# SCH_smart_golf_ball_v2_2024-06-10.net
KiCad netlist of a schematic drawn in EasyEDA
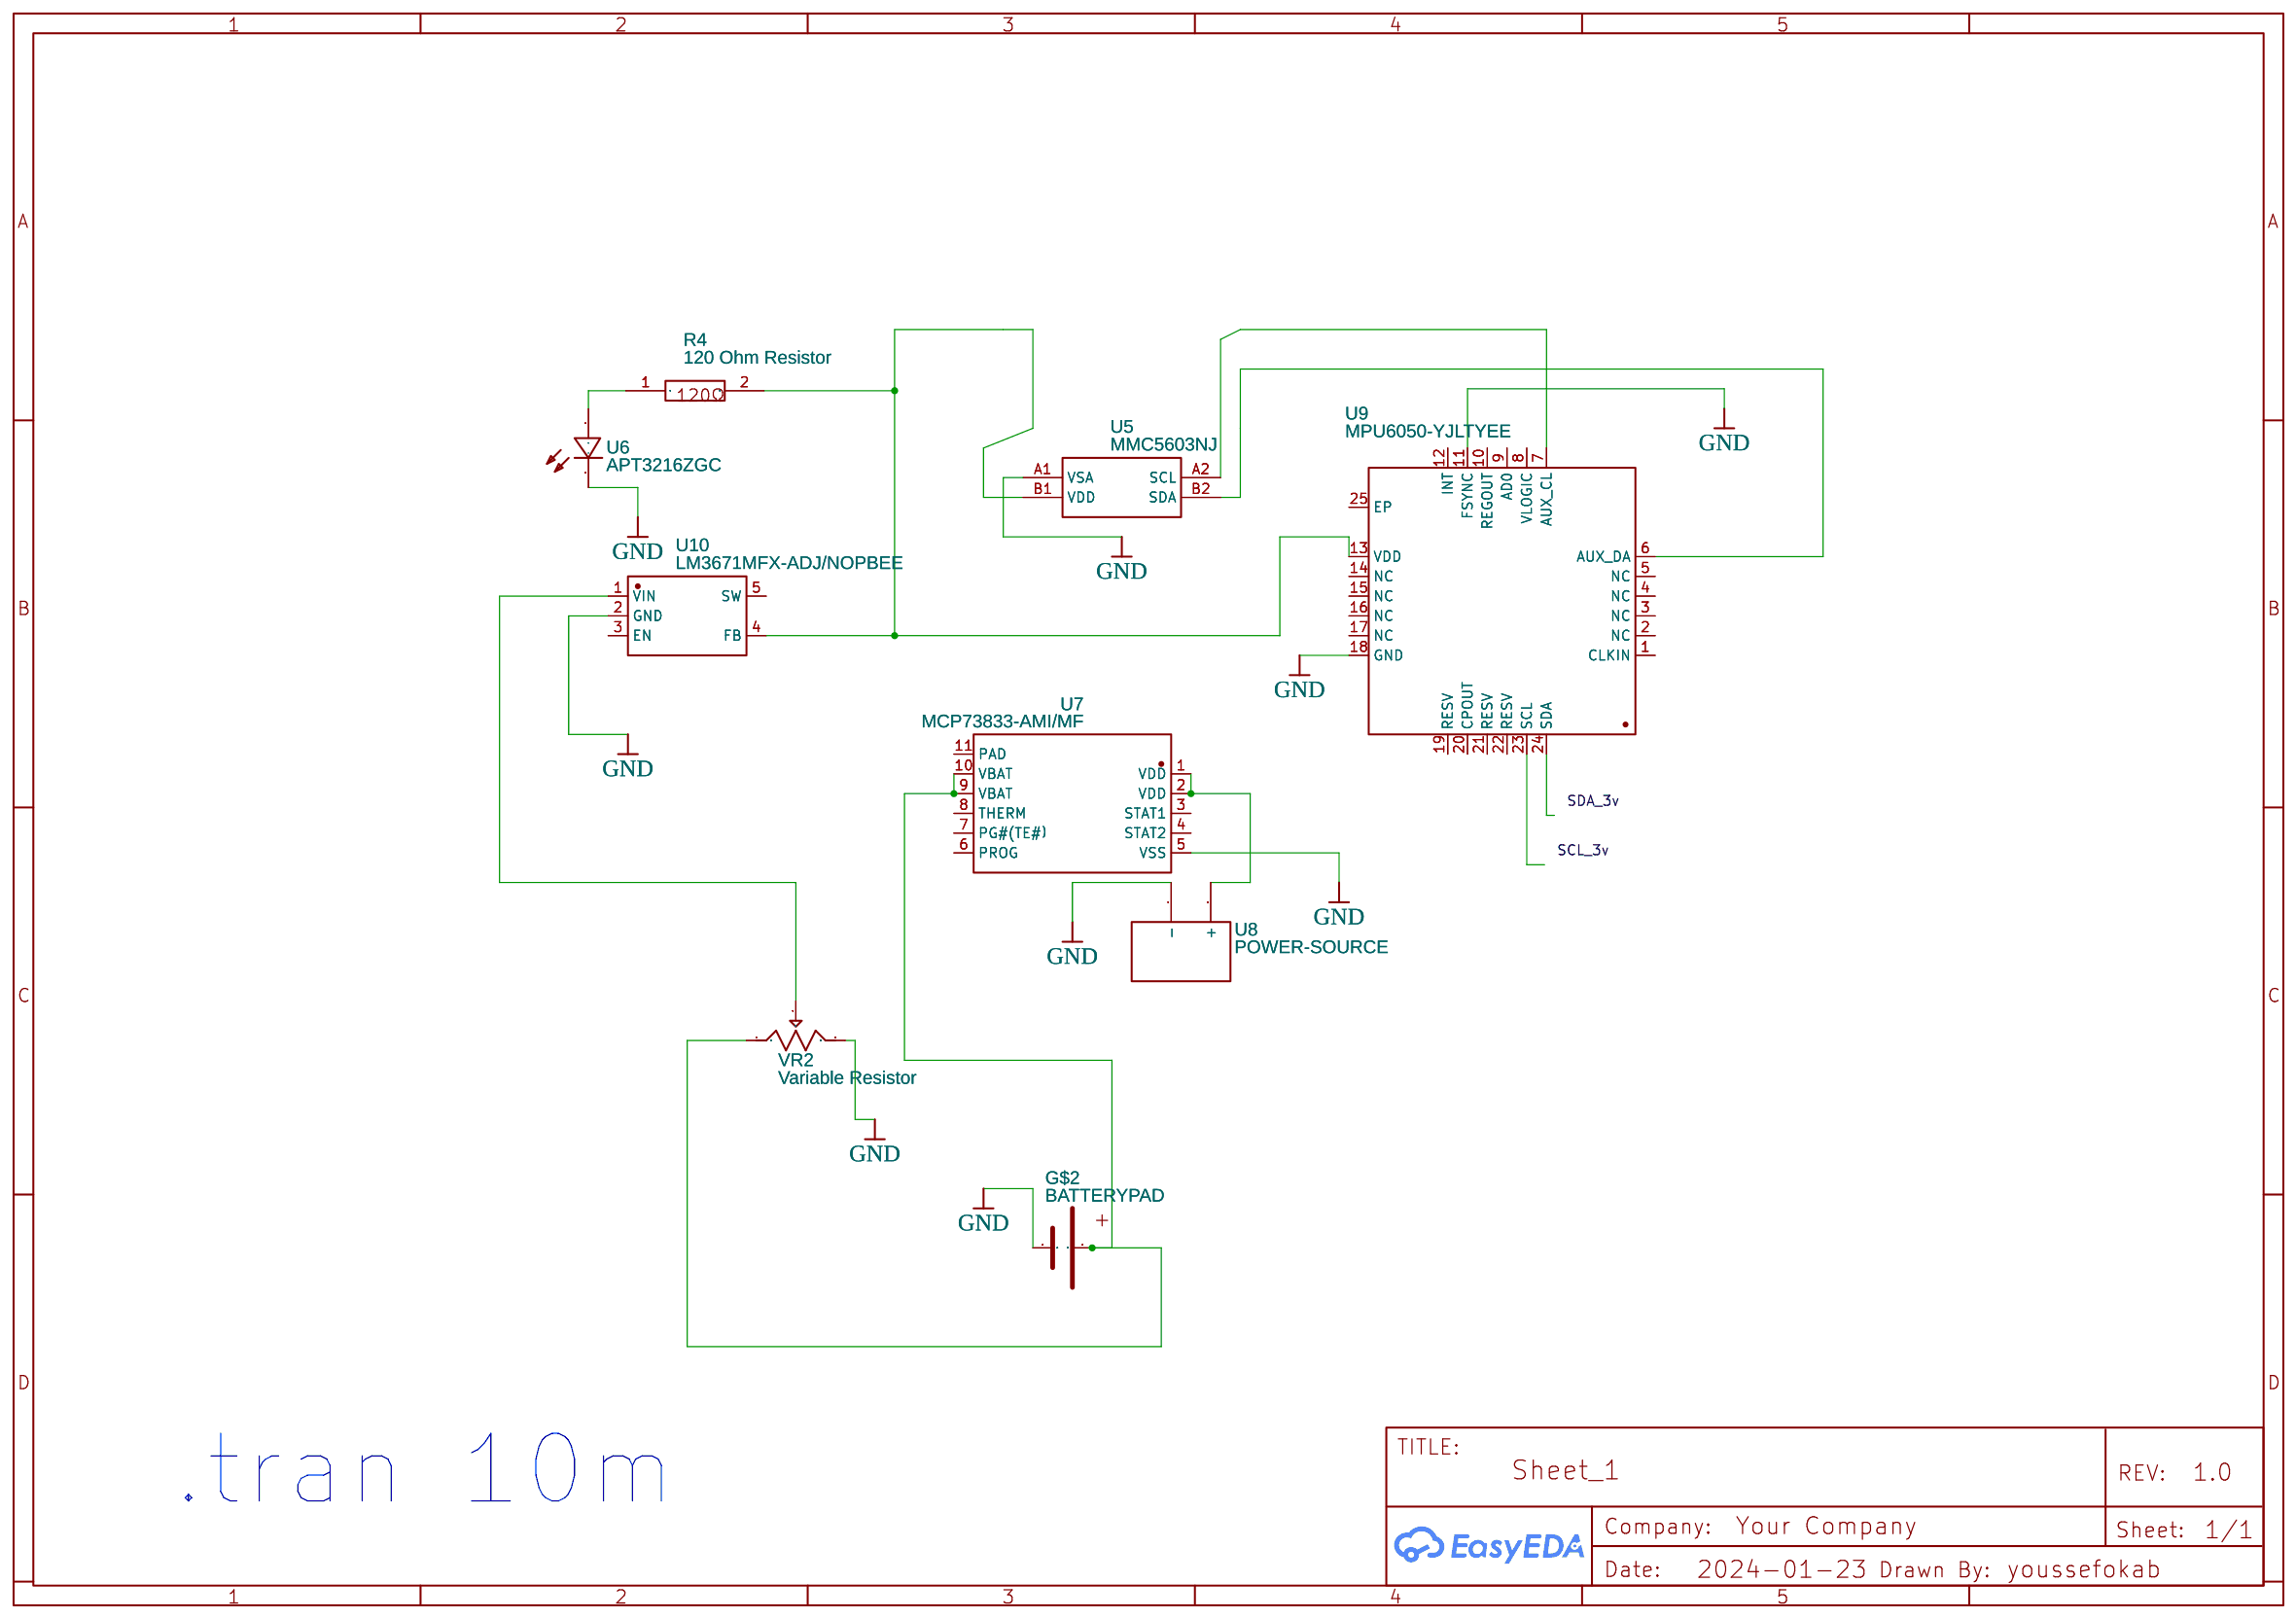
[diagram p0: schematic sheet]

(export (version "E")
  (design (tool "Eeschema 10.0.6"))
  (components
    (comp (ref "G$2") (value "BATTERYPAD") (libsource (lib "") (part "BATTERYPAD")))
    (comp (ref "R4") (value "120 Ohm Resistor") (libsource (lib "") (part "120 Ohm Resistor")))
    (comp (ref "U5")
      (value "MMC5603NJ")
      (fields (field (name "Manufacturer") "MEMSIC(美新)"))
      (libsource (lib "") (part "MMC5603NJ"))
    )
    (comp (ref "U6")
      (value "APT3216ZGC")
      (fields (field (name "Manufacturer") "Kingbright"))
      (libsource (lib "") (part "APT3216ZGC"))
    )
    (comp (ref "U7")
      (value "MCP73833-AMI/MF")
      (fields (field (name "Manufacturer") "MICROCHIP(美国微芯)"))
      (libsource (lib "") (part "MCP73833-AMI/MF"))
    )
    (comp (ref "U8") (value "POWER-SOURCE") (libsource (lib "") (part "POWER-SOURCE")))
    (comp (ref "U9")
      (value "MPU6050-YJLTYEE")
      (fields (field (name "Manufacturer Part") "MPU6050-YJLTY"))
      (libsource (lib "") (part "MPU6050-YJLTY"))
    )
    (comp (ref "U10")
      (value "LM3671MFX-ADJ/NOPBEE")
      (fields
        (field (name "Manufacturer Part") "LM3671MFX-ADJ/NOPB")
        (field (name "Manufacturer") "TI(德州仪器)")
      )
      (libsource (lib "") (part "LM3671MFX-ADJ/NOPB"))
    )
    (comp (ref "VR2")
      (value "Variable Resistor")
      (fields (field (name "Manufacturer Part") "x1"))
      (libsource (lib "") (part "Variable Resistor"))
    )
  )
  (nets
    (net (code "3") (name "GND") (class "Default")
      (node (ref "G$2") (pin "-VE") (pinfunction "-VE_-VE") (pintype "bidirectional"))
      (node (ref "U10") (pin "2") (pinfunction "GND_2") (pintype "unspecified"))
      (node (ref "U5") (pin "A1") (pinfunction "VSA_A1") (pintype "unspecified"))
      (node (ref "U6") (pin "1") (pinfunction "-_1") (pintype "unspecified"))
      (node (ref "U7") (pin "5") (pinfunction "VSS_5") (pintype "unspecified"))
      (node (ref "U8") (pin "1") (pinfunction "-_1") (pintype "unspecified"))
      (node (ref "U9") (pin "11") (pinfunction "FSYNC_11") (pintype "unspecified"))
      (node (ref "U9") (pin "18") (pinfunction "GND_18") (pintype "unspecified"))
      (node (ref "VR2") (pin "3") (pinfunction "3_3") (pintype "unspecified"))
    )
    (net (code "4") (name "Net-(G$2-Pad+VE)") (class "Default")
      (node (ref "G$2") (pin "+VE") (pinfunction "+VE_+VE") (pintype "bidirectional"))
      (node (ref "U7") (pin "10") (pinfunction "VBAT_10") (pintype "unspecified"))
      (node (ref "U7") (pin "9") (pinfunction "VBAT_9") (pintype "unspecified"))
      (node (ref "VR2") (pin "1") (pinfunction "1_1") (pintype "unspecified"))
    )
    (net (code "5") (name "Net-(U5-SCL)") (class "Default")
      (node (ref "U5") (pin "A2") (pinfunction "SCL_A2") (pintype "unspecified"))
      (node (ref "U9") (pin "7") (pinfunction "AUX_CL_7") (pintype "unspecified"))
    )
    (net (code "6") (name "Net-(U5-SDA)") (class "Default")
      (node (ref "U5") (pin "B2") (pinfunction "SDA_B2") (pintype "unspecified"))
      (node (ref "U9") (pin "6") (pinfunction "AUX_DA_6") (pintype "unspecified"))
    )
    (net (code "7") (name "Net-(U6-+)") (class "Default")
      (node (ref "R4") (pin "1") (pinfunction "1_1") (pintype "unspecified"))
      (node (ref "U6") (pin "2") (pinfunction "+_2") (pintype "unspecified"))
    )
    (net (code "8") (name "Net-(U8-+)") (class "Default")
      (node (ref "U7") (pin "1") (pinfunction "VDD_1") (pintype "unspecified"))
      (node (ref "U7") (pin "2") (pinfunction "VDD_2") (pintype "unspecified"))
      (node (ref "U8") (pin "2") (pinfunction "+_2") (pintype "unspecified"))
    )
    (net (code "9") (name "Net-(U10-FB)") (class "Default")
      (node (ref "R4") (pin "2") (pinfunction "2_2") (pintype "unspecified"))
      (node (ref "U10") (pin "4") (pinfunction "FB_4") (pintype "unspecified"))
      (node (ref "U5") (pin "B1") (pinfunction "VDD_B1") (pintype "unspecified"))
      (node (ref "U9") (pin "13") (pinfunction "VDD_13") (pintype "unspecified"))
    )
    (net (code "10") (name "Net-(U10-VIN)") (class "Default")
      (node (ref "U10") (pin "1") (pinfunction "VIN_1") (pintype "unspecified"))
      (node (ref "VR2") (pin "2") (pinfunction "2_2") (pintype "unspecified"))
    )
    (net (code "11") (name "unconnected-(U7-PAD-Pad11)") (class "Default")
      (node (ref "U7") (pin "11") (pinfunction "PAD_11") (pintype "unspecified"))
    )
    (net (code "12") (name "unconnected-(U7-PG#(TE#）-Pad7)") (class "Default")
      (node (ref "U7") (pin "7") (pinfunction "PG#(TE#）_7") (pintype "unspecified"))
    )
    (net (code "13") (name "unconnected-(U7-PROG-Pad6)") (class "Default")
      (node (ref "U7") (pin "6") (pinfunction "PROG_6") (pintype "unspecified"))
    )
    (net (code "14") (name "unconnected-(U7-STAT1-Pad3)") (class "Default")
      (node (ref "U7") (pin "3") (pinfunction "STAT1_3") (pintype "unspecified"))
    )
    (net (code "15") (name "unconnected-(U7-STAT2-Pad4)") (class "Default")
      (node (ref "U7") (pin "4") (pinfunction "STAT2_4") (pintype "unspecified"))
    )
    (net (code "16") (name "unconnected-(U7-THERM-Pad8)") (class "Default")
      (node (ref "U7") (pin "8") (pinfunction "THERM_8") (pintype "unspecified"))
    )
    (net (code "17") (name "unconnected-(U9-AD0-Pad9)") (class "Default")
      (node (ref "U9") (pin "9") (pinfunction "AD0_9") (pintype "unspecified"))
    )
    (net (code "18") (name "unconnected-(U9-CLKIN-Pad1)") (class "Default")
      (node (ref "U9") (pin "1") (pinfunction "CLKIN_1") (pintype "unspecified"))
    )
    (net (code "19") (name "unconnected-(U9-CPOUT-Pad20)") (class "Default")
      (node (ref "U9") (pin "20") (pinfunction "CPOUT_20") (pintype "unspecified"))
    )
    (net (code "20") (name "unconnected-(U9-EP-Pad25)") (class "Default")
      (node (ref "U9") (pin "25") (pinfunction "EP_25") (pintype "unspecified"))
    )
    (net (code "21") (name "unconnected-(U9-INT-Pad12)") (class "Default")
      (node (ref "U9") (pin "12") (pinfunction "INT_12") (pintype "unspecified"))
    )
    (net (code "22") (name "unconnected-(U9-NC-Pad2)") (class "Default")
      (node (ref "U9") (pin "2") (pinfunction "NC_2") (pintype "unspecified"))
    )
    (net (code "23") (name "unconnected-(U9-NC-Pad3)") (class "Default")
      (node (ref "U9") (pin "3") (pinfunction "NC_3") (pintype "unspecified"))
    )
    (net (code "24") (name "unconnected-(U9-NC-Pad4)") (class "Default")
      (node (ref "U9") (pin "4") (pinfunction "NC_4") (pintype "unspecified"))
    )
    (net (code "25") (name "unconnected-(U9-NC-Pad5)") (class "Default")
      (node (ref "U9") (pin "5") (pinfunction "NC_5") (pintype "unspecified"))
    )
    (net (code "26") (name "unconnected-(U9-NC-Pad14)") (class "Default")
      (node (ref "U9") (pin "14") (pinfunction "NC_14") (pintype "unspecified"))
    )
    (net (code "27") (name "unconnected-(U9-NC-Pad15)") (class "Default")
      (node (ref "U9") (pin "15") (pinfunction "NC_15") (pintype "unspecified"))
    )
    (net (code "28") (name "unconnected-(U9-NC-Pad16)") (class "Default")
      (node (ref "U9") (pin "16") (pinfunction "NC_16") (pintype "unspecified"))
    )
    (net (code "29") (name "unconnected-(U9-NC-Pad17)") (class "Default")
      (node (ref "U9") (pin "17") (pinfunction "NC_17") (pintype "unspecified"))
    )
    (net (code "30") (name "unconnected-(U9-REGOUT-Pad10)") (class "Default")
      (node (ref "U9") (pin "10") (pinfunction "REGOUT_10") (pintype "unspecified"))
    )
    (net (code "31") (name "unconnected-(U9-RESV-Pad19)") (class "Default")
      (node (ref "U9") (pin "19") (pinfunction "RESV_19") (pintype "unspecified"))
    )
    (net (code "32") (name "unconnected-(U9-RESV-Pad21)") (class "Default")
      (node (ref "U9") (pin "21") (pinfunction "RESV_21") (pintype "unspecified"))
    )
    (net (code "33") (name "unconnected-(U9-RESV-Pad22)") (class "Default")
      (node (ref "U9") (pin "22") (pinfunction "RESV_22") (pintype "unspecified"))
    )
    (net (code "34") (name "unconnected-(U9-SCL-Pad23)") (class "Default")
      (node (ref "U9") (pin "23") (pinfunction "SCL_23") (pintype "unspecified"))
    )
    (net (code "35") (name "unconnected-(U9-SDA-Pad24)") (class "Default")
      (node (ref "U9") (pin "24") (pinfunction "SDA_24") (pintype "unspecified"))
    )
    (net (code "36") (name "unconnected-(U9-VLOGIC-Pad8)") (class "Default")
      (node (ref "U9") (pin "8") (pinfunction "VLOGIC_8") (pintype "unspecified"))
    )
    (net (code "37") (name "unconnected-(U10-EN-Pad3)") (class "Default")
      (node (ref "U10") (pin "3") (pinfunction "EN_3") (pintype "unspecified"))
    )
    (net (code "38") (name "unconnected-(U10-SW-Pad5)") (class "Default")
      (node (ref "U10") (pin "5") (pinfunction "SW_5") (pintype "unspecified"))
    )
  )
)
